# SCH_heart_2024-08-19.net
KiCad netlist of a schematic drawn in EasyEDA
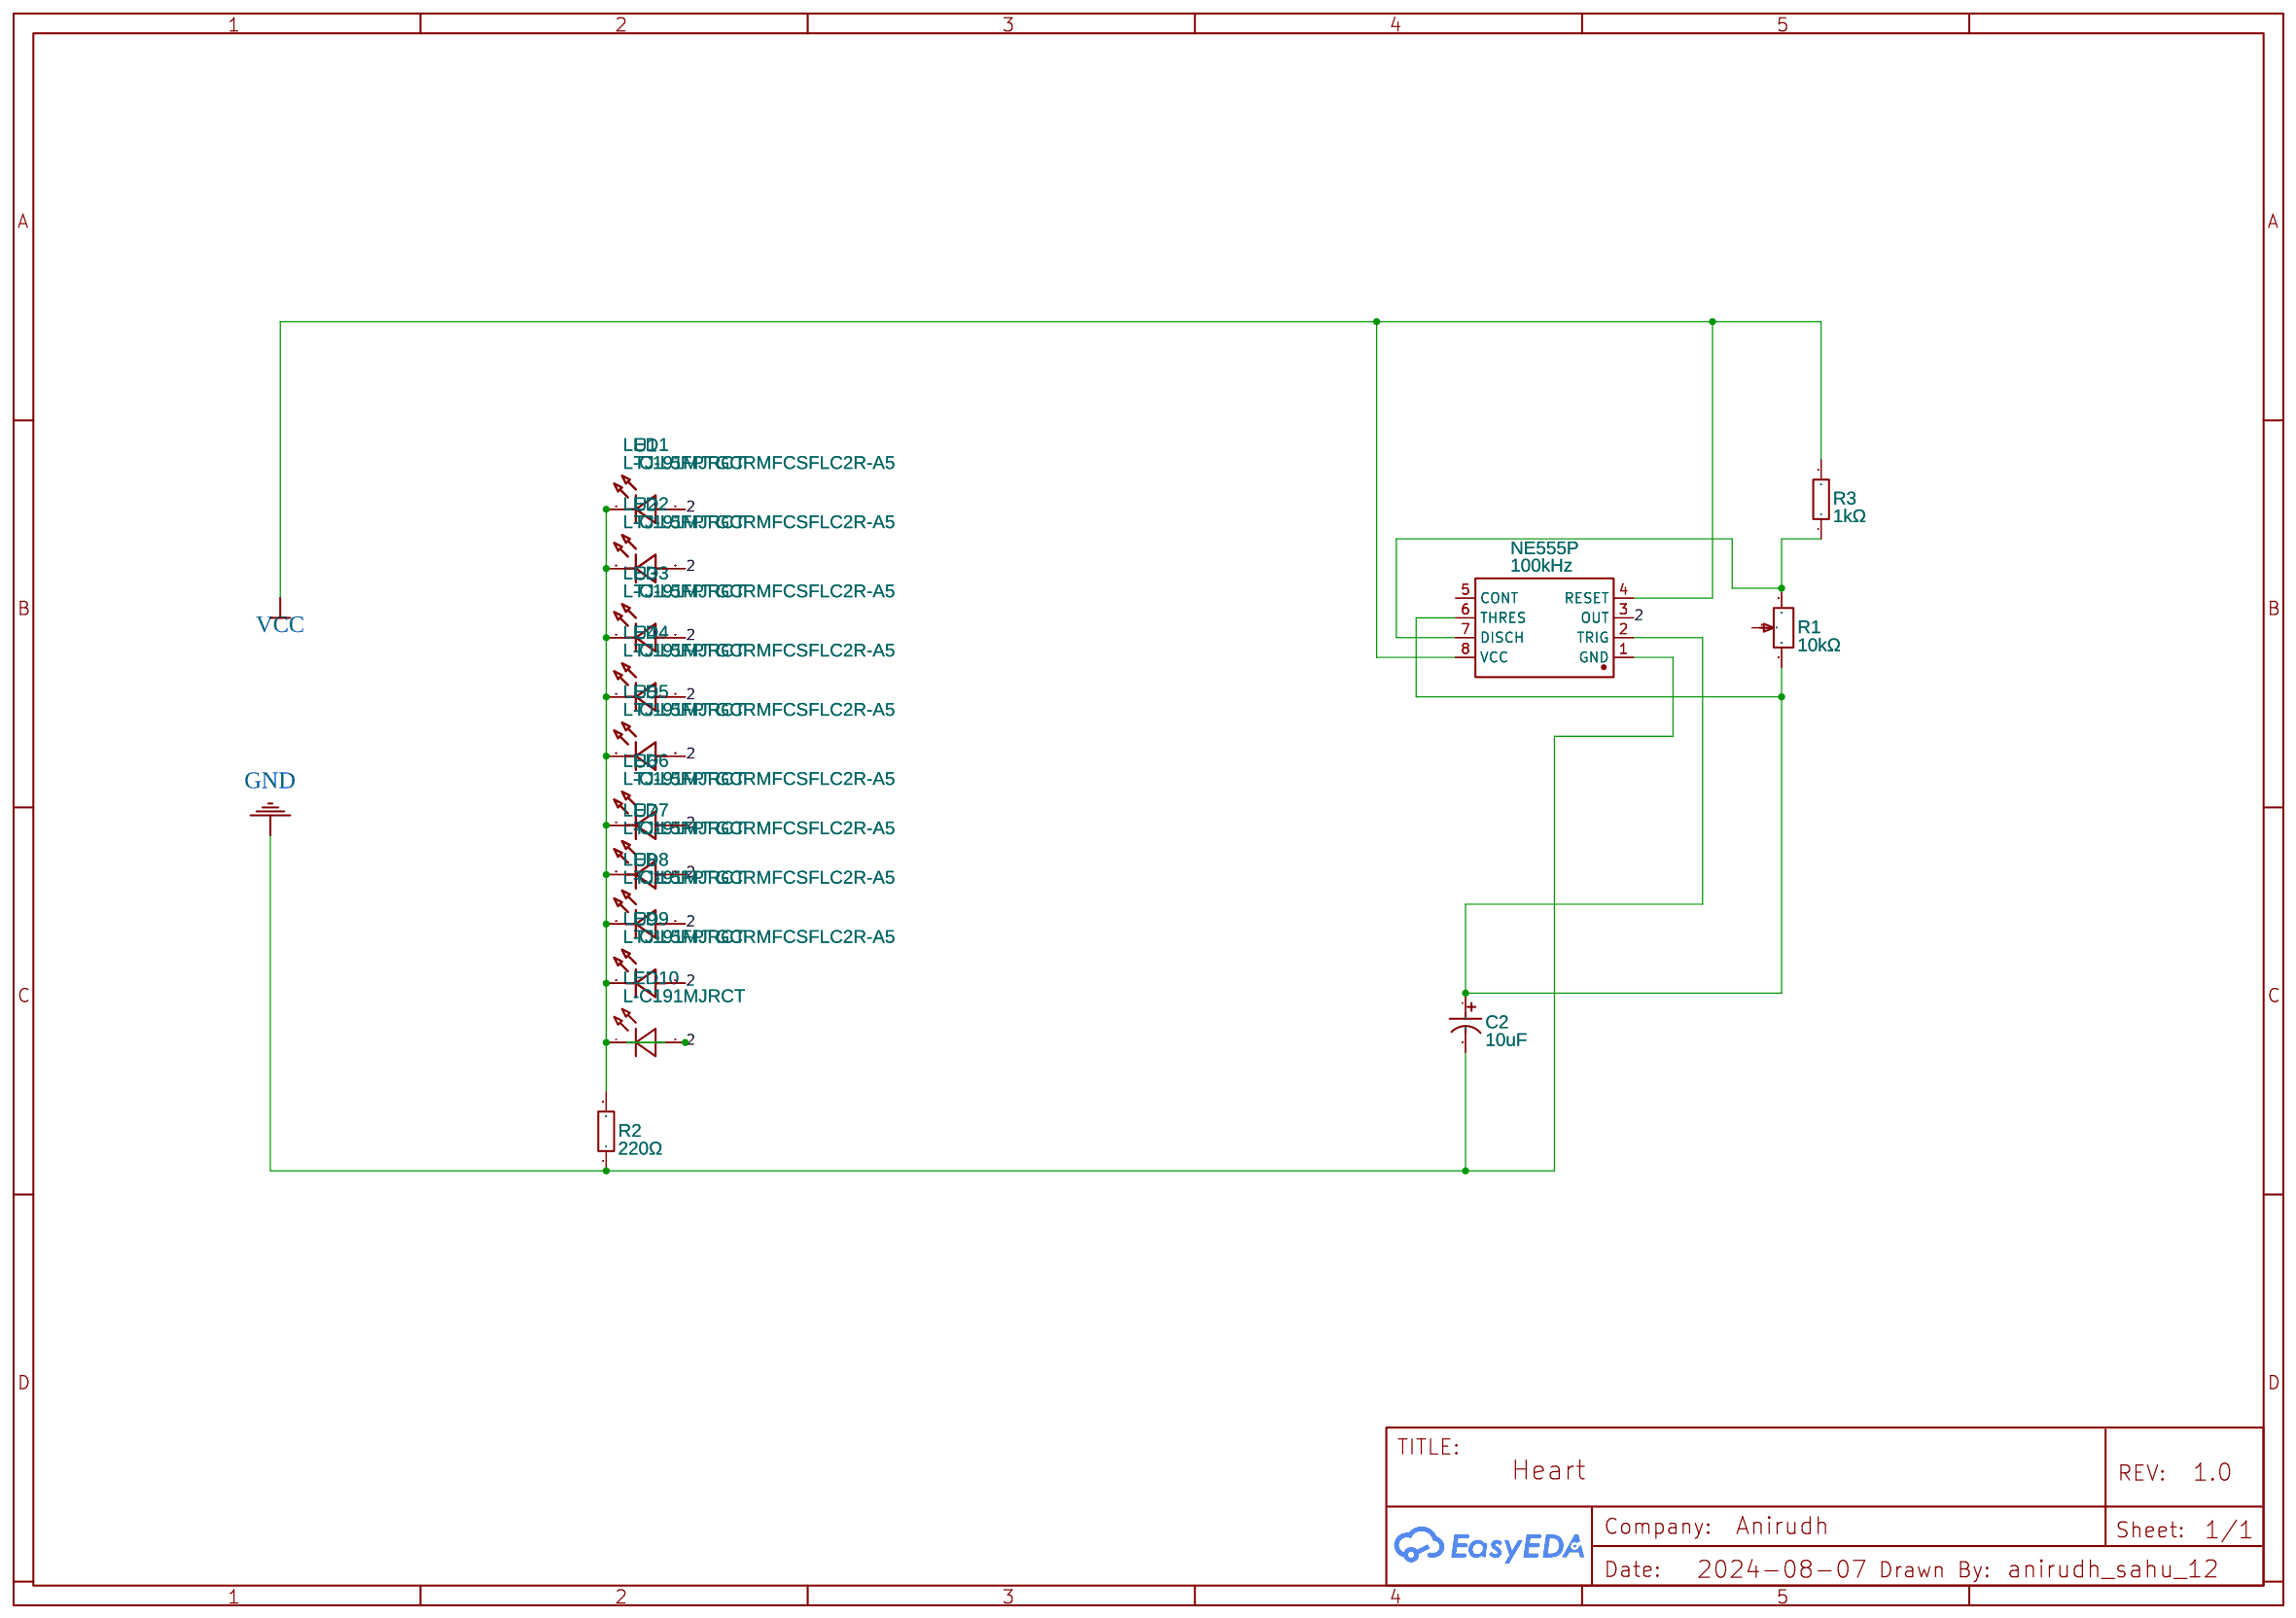
[diagram p0: schematic sheet]

(export (version "E")
  (design (tool "Eeschema 10.0.6"))
  (components
    (comp (ref "C2")
      (value "10uF")
      (fields (field (name "Manufacturer Part") "RVT1H100M0605") (field (name "Manufacturer") "ROQANG(容强)"))
      (libsource (lib "") (part "RVT1H100M0605"))
    )
    (comp (ref "LED1")
      (value "L-C191MJRCT")
      (fields (field (name "Manufacturer") "PARALIGHT(光鼎)"))
      (libsource (lib "") (part "L-C191MJRCT"))
    )
    (comp (ref "LED2")
      (value "L-C191MJRCT")
      (fields (field (name "Manufacturer") "PARALIGHT(光鼎)"))
      (libsource (lib "") (part "L-C191MJRCT"))
    )
    (comp (ref "LED3")
      (value "L-C191MJRCT")
      (fields (field (name "Manufacturer") "PARALIGHT(光鼎)"))
      (libsource (lib "") (part "L-C191MJRCT"))
    )
    (comp (ref "LED4")
      (value "L-C191MJRCT")
      (fields (field (name "Manufacturer") "PARALIGHT(光鼎)"))
      (libsource (lib "") (part "L-C191MJRCT"))
    )
    (comp (ref "LED5")
      (value "L-C191MJRCT")
      (fields (field (name "Manufacturer") "PARALIGHT(光鼎)"))
      (libsource (lib "") (part "L-C191MJRCT"))
    )
    (comp (ref "LED6")
      (value "L-C191MJRCT")
      (fields (field (name "Manufacturer") "PARALIGHT(光鼎)"))
      (libsource (lib "") (part "L-C191MJRCT"))
    )
    (comp (ref "LED7")
      (value "L-C191MJRCT")
      (fields (field (name "Manufacturer") "PARALIGHT(光鼎)"))
      (libsource (lib "") (part "L-C191MJRCT"))
    )
    (comp (ref "LED8")
      (value "L-C191MJRCT")
      (fields (field (name "Manufacturer") "PARALIGHT(光鼎)"))
      (libsource (lib "") (part "L-C191MJRCT"))
    )
    (comp (ref "LED9")
      (value "L-C191MJRCT")
      (fields (field (name "Manufacturer") "PARALIGHT(光鼎)"))
      (libsource (lib "") (part "L-C191MJRCT"))
    )
    (comp (ref "LED10")
      (value "L-C191MJRCT")
      (fields (field (name "Manufacturer") "PARALIGHT(光鼎)"))
      (libsource (lib "") (part "L-C191MJRCT"))
    )
    (comp (ref "NE555P")
      (value "100kHz")
      (fields (field (name "Manufacturer Part") "NE555P") (field (name "Manufacturer") "TI(德州仪器)"))
      (libsource (lib "") (part "NE555P"))
    )
    (comp (ref "R1")
      (value "10kΩ")
      (fields (field (name "Manufacturer Part") "3296W-1-103LF") (field (name "Manufacturer") "BOURNS"))
      (libsource (lib "") (part "3296W-1-103LF"))
    )
    (comp (ref "R2")
      (value "220Ω")
      (fields
        (field (name "Manufacturer Part") "MFR02SF2200A10")
        (field (name "Manufacturer") "UNI-ROYAL(厚声)")
      )
      (libsource (lib "") (part "MFR02SF2200A10"))
    )
    (comp (ref "R3")
      (value "1kΩ")
      (fields
        (field (name "Manufacturer Part") "MFR01SF1001A10")
        (field (name "Manufacturer") "UNI-ROYAL(厚声)")
      )
      (libsource (lib "") (part "MFR01SF1001A10"))
    )
    (comp (ref "U1")
      (value "TJ-L5FPTGCRMFCSFLC2R-A5")
      (fields (field (name "Manufacturer") "TOGIALED(统佳)"))
      (libsource (lib "") (part "TJ-L5FPTGCRMFCSFLC2R-A5"))
    )
    (comp (ref "U2")
      (value "TJ-L5FPTGCRMFCSFLC2R-A5")
      (fields (field (name "Manufacturer") "TOGIALED(统佳)"))
      (libsource (lib "") (part "TJ-L5FPTGCRMFCSFLC2R-A5"))
    )
    (comp (ref "U3")
      (value "TJ-L5FPTGCRMFCSFLC2R-A5")
      (fields (field (name "Manufacturer") "TOGIALED(统佳)"))
      (libsource (lib "") (part "TJ-L5FPTGCRMFCSFLC2R-A5"))
    )
    (comp (ref "U4")
      (value "TJ-L5FPTGCRMFCSFLC2R-A5")
      (fields (field (name "Manufacturer") "TOGIALED(统佳)"))
      (libsource (lib "") (part "TJ-L5FPTGCRMFCSFLC2R-A5"))
    )
    (comp (ref "U5")
      (value "TJ-L5FPTGCRMFCSFLC2R-A5")
      (fields (field (name "Manufacturer") "TOGIALED(统佳)"))
      (libsource (lib "") (part "TJ-L5FPTGCRMFCSFLC2R-A5"))
    )
    (comp (ref "U6")
      (value "TJ-L5FPTGCRMFCSFLC2R-A5")
      (fields (field (name "Manufacturer") "TOGIALED(统佳)"))
      (libsource (lib "") (part "TJ-L5FPTGCRMFCSFLC2R-A5"))
    )
    (comp (ref "U7")
      (value "TJ-L5FPTGCRMFCSFLC2R-A5")
      (fields (field (name "Manufacturer") "TOGIALED(统佳)"))
      (libsource (lib "") (part "TJ-L5FPTGCRMFCSFLC2R-A5"))
    )
    (comp (ref "U8")
      (value "TJ-L5FPTGCRMFCSFLC2R-A5")
      (fields (field (name "Manufacturer") "TOGIALED(统佳)"))
      (libsource (lib "") (part "TJ-L5FPTGCRMFCSFLC2R-A5"))
    )
    (comp (ref "U9")
      (value "TJ-L5FPTGCRMFCSFLC2R-A5")
      (fields (field (name "Manufacturer") "TOGIALED(统佳)"))
      (libsource (lib "") (part "TJ-L5FPTGCRMFCSFLC2R-A5"))
    )
  )
  (nets
    (net (code "1") (name "/2") (class "Default")
      (node (ref "LED1") (pin "1") (pinfunction "K_1") (pintype "unspecified"))
      (node (ref "LED1") (pin "2") (pinfunction "A_2") (pintype "unspecified"))
      (node (ref "LED10") (pin "1") (pinfunction "K_1") (pintype "unspecified"))
      (node (ref "LED10") (pin "2") (pinfunction "A_2") (pintype "unspecified"))
      (node (ref "LED2") (pin "1") (pinfunction "K_1") (pintype "unspecified"))
      (node (ref "LED2") (pin "2") (pinfunction "A_2") (pintype "unspecified"))
      (node (ref "LED3") (pin "1") (pinfunction "K_1") (pintype "unspecified"))
      (node (ref "LED3") (pin "2") (pinfunction "A_2") (pintype "unspecified"))
      (node (ref "LED4") (pin "1") (pinfunction "K_1") (pintype "unspecified"))
      (node (ref "LED4") (pin "2") (pinfunction "A_2") (pintype "unspecified"))
      (node (ref "LED5") (pin "1") (pinfunction "K_1") (pintype "unspecified"))
      (node (ref "LED5") (pin "2") (pinfunction "A_2") (pintype "unspecified"))
      (node (ref "LED6") (pin "1") (pinfunction "K_1") (pintype "unspecified"))
      (node (ref "LED6") (pin "2") (pinfunction "A_2") (pintype "unspecified"))
      (node (ref "LED7") (pin "1") (pinfunction "K_1") (pintype "unspecified"))
      (node (ref "LED7") (pin "2") (pinfunction "A_2") (pintype "unspecified"))
      (node (ref "LED8") (pin "1") (pinfunction "K_1") (pintype "unspecified"))
      (node (ref "LED8") (pin "2") (pinfunction "A_2") (pintype "unspecified"))
      (node (ref "LED9") (pin "1") (pinfunction "K_1") (pintype "unspecified"))
      (node (ref "LED9") (pin "2") (pinfunction "A_2") (pintype "unspecified"))
      (node (ref "NE555P") (pin "3") (pinfunction "OUT_3") (pintype "unspecified"))
      (node (ref "R2") (pin "2") (pinfunction "2_2") (pintype "input"))
      (node (ref "U1") (pin "1") (pinfunction "A_1") (pintype "unspecified"))
      (node (ref "U1") (pin "2") (pinfunction "K_2") (pintype "unspecified"))
      (node (ref "U2") (pin "1") (pinfunction "A_1") (pintype "unspecified"))
      (node (ref "U2") (pin "2") (pinfunction "K_2") (pintype "unspecified"))
      (node (ref "U3") (pin "1") (pinfunction "A_1") (pintype "unspecified"))
      (node (ref "U3") (pin "2") (pinfunction "K_2") (pintype "unspecified"))
      (node (ref "U4") (pin "1") (pinfunction "A_1") (pintype "unspecified"))
      (node (ref "U4") (pin "2") (pinfunction "K_2") (pintype "unspecified"))
      (node (ref "U5") (pin "1") (pinfunction "A_1") (pintype "unspecified"))
      (node (ref "U5") (pin "2") (pinfunction "K_2") (pintype "unspecified"))
      (node (ref "U6") (pin "1") (pinfunction "A_1") (pintype "unspecified"))
      (node (ref "U6") (pin "2") (pinfunction "K_2") (pintype "unspecified"))
      (node (ref "U7") (pin "1") (pinfunction "A_1") (pintype "unspecified"))
      (node (ref "U7") (pin "2") (pinfunction "K_2") (pintype "unspecified"))
      (node (ref "U8") (pin "1") (pinfunction "A_1") (pintype "unspecified"))
      (node (ref "U8") (pin "2") (pinfunction "K_2") (pintype "unspecified"))
      (node (ref "U9") (pin "1") (pinfunction "A_1") (pintype "unspecified"))
      (node (ref "U9") (pin "2") (pinfunction "K_2") (pintype "unspecified"))
    )
    (net (code "2") (name "GND") (class "Default")
      (node (ref "C2") (pin "2") (pinfunction "2_2") (pintype "input"))
      (node (ref "NE555P") (pin "1") (pinfunction "GND_1") (pintype "unspecified"))
      (node (ref "R2") (pin "1") (pinfunction "1_1") (pintype "input"))
    )
    (net (code "3") (name "Net-(NE555P-DISCH)") (class "Default")
      (node (ref "NE555P") (pin "7") (pinfunction "DISCH_7") (pintype "unspecified"))
      (node (ref "R1") (pin "1") (pinfunction "1_1") (pintype "input"))
      (node (ref "R3") (pin "1") (pinfunction "1_1") (pintype "input"))
    )
    (net (code "4") (name "Net-(NE555P-THRES)") (class "Default")
      (node (ref "C2") (pin "1") (pinfunction "1_1") (pintype "input"))
      (node (ref "NE555P") (pin "2") (pinfunction "TRIG_2") (pintype "unspecified"))
      (node (ref "NE555P") (pin "6") (pinfunction "THRES_6") (pintype "unspecified"))
      (node (ref "R1") (pin "3") (pinfunction "3_3") (pintype "input"))
    )
    (net (code "5") (name "VCC") (class "Default")
      (node (ref "NE555P") (pin "4") (pinfunction "RESET_4") (pintype "unspecified"))
      (node (ref "NE555P") (pin "8") (pinfunction "VCC_8") (pintype "unspecified"))
      (node (ref "R3") (pin "2") (pinfunction "2_2") (pintype "input"))
    )
    (net (code "6") (name "unconnected-(NE555P-CONT-Pad5)") (class "Default")
      (node (ref "NE555P") (pin "5") (pinfunction "CONT_5") (pintype "unspecified"))
    )
    (net (code "7") (name "unconnected-(R1-Pad2)") (class "Default")
      (node (ref "R1") (pin "2") (pinfunction "2_2") (pintype "input"))
    )
  )
)
